# PlantSensor_V02_Schematic.net
KiCad netlist of a schematic drawn in Altium Designer
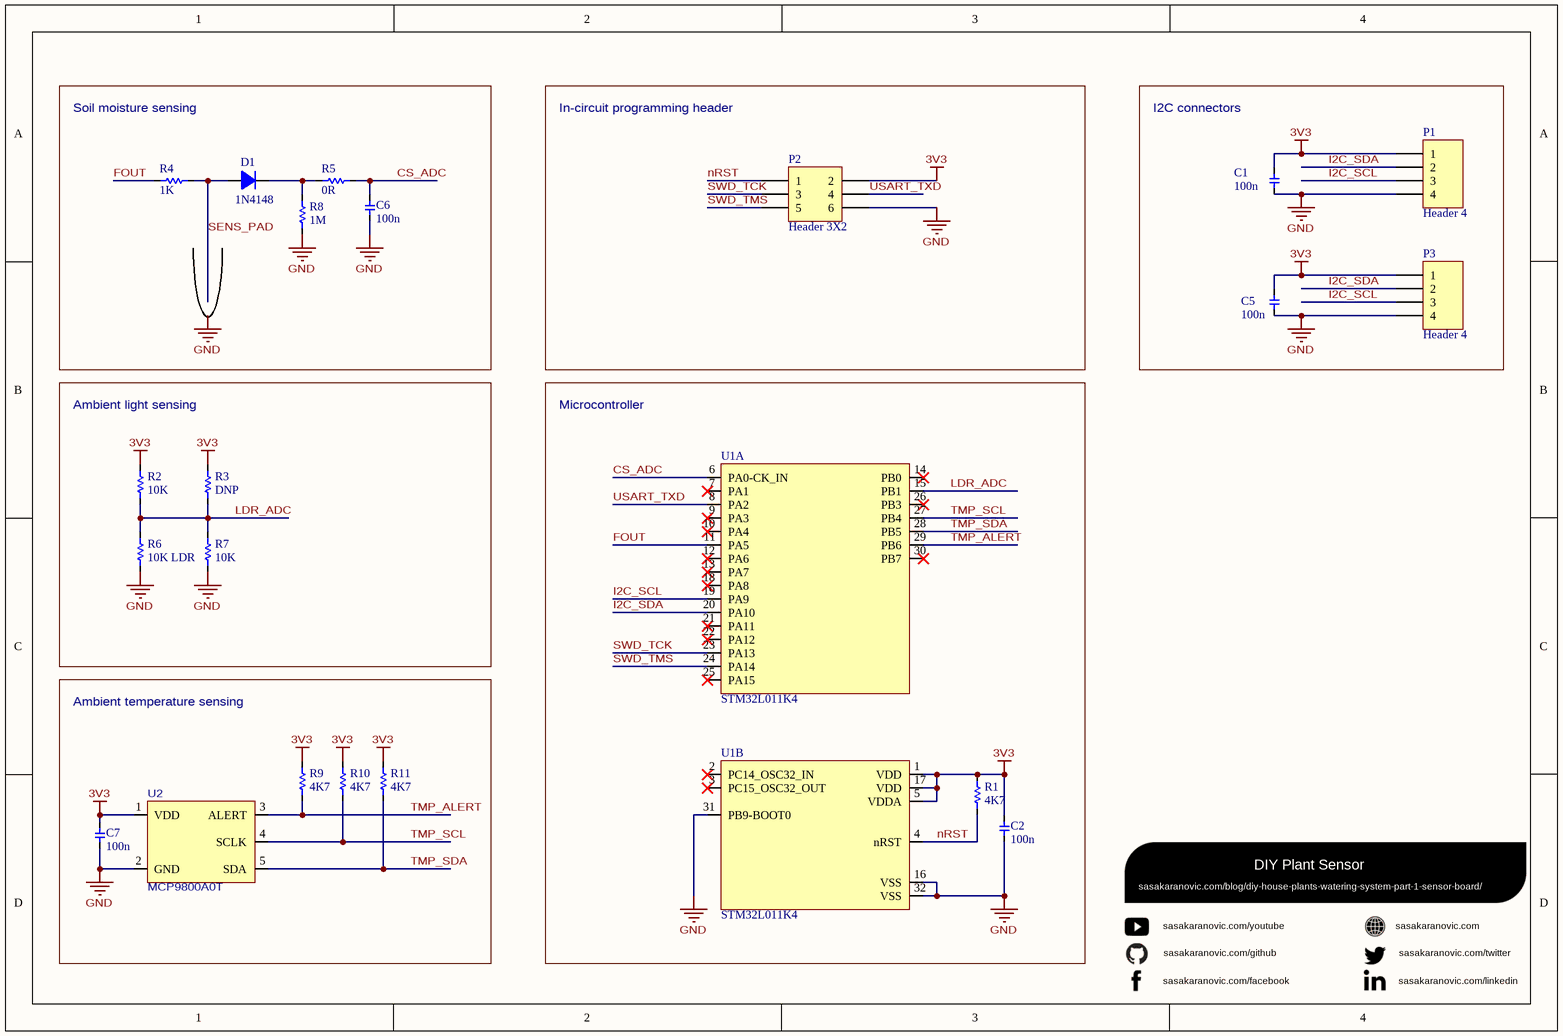
[diagram p0: PlantSensor_V02_Schematic.SchDoc]

(export (version "E")
  (design (tool "Eeschema 10.0.6"))
  (components
    (comp (ref "C1")
      (value "100n")
      (footprint "Moji Footprintovi:0603 - CAP")
      (description "CAP CER 0.1UF 50V X7R 0603")
      (fields
        (field (name "MANUFACTURER") "Samsung Electro-Mechanics")
        (field (name "MANUFACTURER PART NUMBER") "CL10B104KB8NNNL")
      )
      (libsource (lib "Moji Schematici") (part "Cap"))
    )
    (comp (ref "C2")
      (value "100n")
      (footprint "Moji Footprintovi:0603 - CAP")
      (description "CAP CER 0.1UF 50V X7R 0603")
      (fields
        (field (name "MANUFACTURER") "Samsung Electro-Mechanics")
        (field (name "MANUFACTURER PART NUMBER") "CL10B104KB8NNNL")
      )
      (libsource (lib "Moji Schematici") (part "Cap"))
    )
    (comp (ref "C5")
      (value "100n")
      (footprint "Moji Footprintovi:0603 - CAP")
      (description "CAP CER 0.1UF 50V X7R 0603")
      (fields
        (field (name "MANUFACTURER") "Samsung Electro-Mechanics")
        (field (name "MANUFACTURER PART NUMBER") "CL10B104KB8NNNL")
      )
      (libsource (lib "Moji Schematici") (part "Cap"))
    )
    (comp (ref "C6")
      (value "100n")
      (footprint "Moji Footprintovi:0603 - CAP")
      (description "CAP CER 0.1UF 50V X7R 0603")
      (fields
        (field (name "MANUFACTURER") "Samsung Electro-Mechanics")
        (field (name "MANUFACTURER PART NUMBER") "CL10B104KB8NNNL")
      )
      (libsource (lib "Moji Schematici") (part "Cap"))
    )
    (comp (ref "C7")
      (value "100n")
      (footprint "Moji Footprintovi:0603 - CAP")
      (description "CAP CER 0.1UF 50V X7R 0603")
      (fields
        (field (name "MANUFACTURER") "Samsung Electro-Mechanics")
        (field (name "MANUFACTURER PART NUMBER") "CL10B104KB8NNNL")
      )
      (libsource (lib "Moji Schematici") (part "Cap"))
    )
    (comp (ref "D1")
      (value "1N4148")
      (footprint "Moji Footprintovi:SOD123")
      (description "DIODE GEN PURP 100V 300MA SOD123")
      (fields
        (field (name "DISTRIBUTOR PART NUMBER") "1N4148W-FDICT-ND")
        (field (name "MANUFACTURER") "Diodes Incorporated")
      )
      (libsource (lib "Moji Schematici (1)") (part "Diode"))
    )
    (comp (ref "P1")
      (value "Header 4")
      (footprint "Moji Footprintovi:Header 4x1")
      (description "CONN HEADER VERT 4POS 2.54MM")
      (fields
        (field (name "DISTRIBUTOR PART NUMBER") "732-5317-ND")
        (field (name "MANUFACTURER") "Würth Elektronik")
      )
      (libsource (lib "Moji Schematici") (part "Header 4"))
    )
    (comp (ref "P2")
      (value "Header 3X2")
      (footprint "HDR2X3")
      (description "CONN HEADER VERT 6POS 2.54MM")
      (fields
        (field (name "DISTRIBUTOR PART NUMBER") "2057-PH2-06-UA-ND")
        (field (name "MANUFACTURER") "Adam Tech")
      )
      (libsource (lib "Miscellaneous Connectors") (part "Header 3X2"))
    )
    (comp (ref "P3")
      (value "Header 4")
      (footprint "Moji Footprintovi:Header 4x1")
      (description "CONN HEADER VERT 4POS 2.54MM")
      (fields
        (field (name "DISTRIBUTOR PART NUMBER") "732-5317-ND")
        (field (name "MANUFACTURER") "Würth Elektronik")
      )
      (libsource (lib "Moji Schematici") (part "Header 4"))
    )
    (comp (ref "R1")
      (value "4K7")
      (footprint "Moji Footprintovi:0603")
      (description "RES SMD 4.7K OHM 1% 1/10W 0603")
      (fields
        (field (name "DISTRIBUTOR PART NUMBER") "311-4.70KHRCT-ND")
        (field (name "MANUFACTURER") "Yageo")
      )
      (libsource (lib "Moji Schematici") (part "Res"))
    )
    (comp (ref "R2")
      (value "10K")
      (footprint "Moji Footprintovi:0603")
      (description "RES SMD 10K OHM 1% 1/10W 0603")
      (fields (field (name "DISTRIBUTOR PART NUMBER") "311-10KLDCT-ND") (field (name "MANUFACTURER") "Yageo"))
      (libsource (lib "Moji Schematici") (part "Res"))
    )
    (comp (ref "R3")
      (value "DNP")
      (footprint "Moji Footprintovi:0603")
      (description "Resistor")
      (fields (field (name "Comment") "Res"))
      (libsource (lib "Moji Schematici") (part "Res"))
    )
    (comp (ref "R4")
      (value "1K")
      (footprint "Moji Footprintovi:0603")
      (description "RES SMD 1K OHM 1% 1/10W 0603")
      (fields (field (name "DISTRIBUTOR PART NUMBER") "YAG2323CT-ND") (field (name "MANUFACTURER") "Yageo"))
      (libsource (lib "Moji Schematici") (part "Res"))
    )
    (comp (ref "R5")
      (value "0R")
      (footprint "Moji Footprintovi:0603")
      (description "RES SMD 0 OHM JUMPER 1/10W 0603")
      (fields (field (name "DISTRIBUTOR PART NUMBER") "311-0.0LECT-ND") (field (name "MANUFACTURER") "Yageo"))
      (libsource (lib "Moji Schematici") (part "Res"))
    )
    (comp (ref "R6")
      (value "10K LDR")
      (footprint "Moji Footprintovi:Radial0.1 - SMT")
      (description "PHOTOCELL CDS 400OHM TO-18")
      (fields
        (field (name "DISTRIBUTOR PART NUMBER") "NSL-5152-ND")
        (field (name "MANUFACTURER") "Advanced Photonix")
      )
      (libsource (lib "Moji Schematici") (part "Res"))
    )
    (comp (ref "R7")
      (value "10K")
      (footprint "Moji Footprintovi:0603")
      (description "RES SMD 10K OHM 1% 1/10W 0603")
      (fields (field (name "DISTRIBUTOR PART NUMBER") "311-10KLDCT-ND") (field (name "MANUFACTURER") "Yageo"))
      (libsource (lib "Moji Schematici") (part "Res"))
    )
    (comp (ref "R8")
      (value "1M")
      (footprint "Moji Footprintovi:0603")
      (description "RES SMD 1M OHM 5% 1/10W 0603")
      (fields
        (field (name "DISTRIBUTOR PART NUMBER") "311-1.0MGRCT-ND")
        (field (name "MANUFACTURER") "Yageo")
      )
      (libsource (lib "Moji Schematici") (part "Res"))
    )
    (comp (ref "R9")
      (value "4K7")
      (footprint "Moji Footprintovi:0603")
      (description "RES SMD 4.7K OHM 1% 1/10W 0603")
      (fields
        (field (name "DISTRIBUTOR PART NUMBER") "311-4.70KHRCT-ND")
        (field (name "MANUFACTURER") "Yageo")
      )
      (libsource (lib "Moji Schematici") (part "Res"))
    )
    (comp (ref "R10")
      (value "4K7")
      (footprint "Moji Footprintovi:0603")
      (description "RES SMD 4.7K OHM 1% 1/10W 0603")
      (fields
        (field (name "DISTRIBUTOR PART NUMBER") "311-4.70KHRCT-ND")
        (field (name "MANUFACTURER") "Yageo")
      )
      (libsource (lib "Moji Schematici") (part "Res"))
    )
    (comp (ref "R11")
      (value "4K7")
      (footprint "Moji Footprintovi:0603")
      (description "RES SMD 4.7K OHM 1% 1/10W 0603")
      (fields
        (field (name "DISTRIBUTOR PART NUMBER") "311-4.70KHRCT-ND")
        (field (name "MANUFACTURER") "Yageo")
      )
      (libsource (lib "Moji Schematici") (part "Res"))
    )
    (comp (ref "U1")
      (value "STM32L011K4")
      (footprint "Moji Footprintovi:TQFP80P900X900X160-32N")
      (description "IC MCU 32BIT 16KB FLASH 32LQFP")
      (fields
        (field (name "DISTRIBUTOR PART NUMBER") "497-17480-ND")
        (field (name "MANUFACTURER") "STMicroelectronics")
      )
      (libsource (lib "Moji Schematici (1)") (part "STM32L011K4"))
    )
    (comp (ref "U2")
      (value "MCP9800A0T")
      (footprint "Moji Footprintovi:SOT95P270X145-5N")
      (description "SENSOR DIGITAL -55C-125C SOT23-5")
      (fields
        (field (name "MANUFACTURER") "Microchip Technology")
        (field (name "DISTRIBUTOR PART NUMBER") "MCP9800A0T-M/OTCT-ND")
      )
      (libsource (lib "Moji Schematici") (part "MCP9800A0T-M/OT"))
    )
  )
  (nets
    (net (code "1") (name "/CS_ADC") (class "Default")
      (node (ref "C6") (pin "2") (pinfunction "2_2") (pintype "passive"))
      (node (ref "R5") (pin "2") (pinfunction "2_2") (pintype "passive"))
      (node (ref "U1") (pin "6") (pinfunction "PA0-CK_IN_6") (pintype "passive"))
    )
    (net (code "2") (name "/FOUT") (class "Default")
      (node (ref "R4") (pin "1") (pinfunction "1_1") (pintype "passive"))
      (node (ref "U1") (pin "11") (pinfunction "PA5_11") (pintype "passive"))
    )
    (net (code "3") (name "/I2C_SCL") (class "Default")
      (node (ref "P1") (pin "3") (pinfunction "3_3") (pintype "passive"))
      (node (ref "P3") (pin "3") (pinfunction "3_3") (pintype "passive"))
      (node (ref "U1") (pin "19") (pinfunction "PA9_19") (pintype "passive"))
    )
    (net (code "4") (name "/I2C_SDA") (class "Default")
      (node (ref "P1") (pin "2") (pinfunction "2_2") (pintype "passive"))
      (node (ref "P3") (pin "2") (pinfunction "2_2") (pintype "passive"))
      (node (ref "U1") (pin "20") (pinfunction "PA10_20") (pintype "passive"))
    )
    (net (code "5") (name "/LDR_ADC") (class "Default")
      (node (ref "R2") (pin "1") (pinfunction "1_1") (pintype "passive"))
      (node (ref "R3") (pin "1") (pinfunction "1_1") (pintype "passive"))
      (node (ref "R6") (pin "2") (pinfunction "2_2") (pintype "passive"))
      (node (ref "R7") (pin "2") (pinfunction "2_2") (pintype "passive"))
      (node (ref "U1") (pin "15") (pinfunction "PB1_15") (pintype "passive"))
    )
    (net (code "6") (name "/SENS_PAD") (class "Default")
      (node (ref "D1") (pin "A") (pinfunction "A_A") (pintype "passive"))
      (node (ref "R4") (pin "2") (pinfunction "2_2") (pintype "passive"))
    )
    (net (code "7") (name "/SWD_TCK") (class "Default")
      (node (ref "P2") (pin "3") (pinfunction "3_3") (pintype "passive"))
      (node (ref "U1") (pin "23") (pinfunction "PA13_23") (pintype "passive"))
    )
    (net (code "8") (name "/SWD_TMS") (class "Default")
      (node (ref "P2") (pin "5") (pinfunction "5_5") (pintype "passive"))
      (node (ref "U1") (pin "24") (pinfunction "PA14_24") (pintype "passive"))
    )
    (net (code "9") (name "/TMP_ALERT") (class "Default")
      (node (ref "R9") (pin "1") (pinfunction "1_1") (pintype "passive"))
      (node (ref "U1") (pin "29") (pinfunction "PB6_29") (pintype "passive"))
      (node (ref "U2") (pin "3") (pinfunction "ALERT_3") (pintype "passive"))
    )
    (net (code "10") (name "/TMP_SCL") (class "Default")
      (node (ref "R10") (pin "1") (pinfunction "1_1") (pintype "passive"))
      (node (ref "U1") (pin "27") (pinfunction "PB4_27") (pintype "passive"))
      (node (ref "U2") (pin "4") (pinfunction "SCLK_4") (pintype "passive"))
    )
    (net (code "11") (name "/TMP_SDA") (class "Default")
      (node (ref "R11") (pin "1") (pinfunction "1_1") (pintype "passive"))
      (node (ref "U1") (pin "28") (pinfunction "PB5_28") (pintype "passive"))
      (node (ref "U2") (pin "5") (pinfunction "SDA_5") (pintype "passive"))
    )
    (net (code "12") (name "/USART_TXD") (class "Default")
      (node (ref "P2") (pin "4") (pinfunction "4_4") (pintype "passive"))
      (node (ref "U1") (pin "8") (pinfunction "PA2_8") (pintype "passive"))
    )
    (net (code "13") (name "/nRST") (class "Default")
      (node (ref "P2") (pin "1") (pinfunction "1_1") (pintype "passive"))
      (node (ref "R1") (pin "1") (pinfunction "1_1") (pintype "passive"))
      (node (ref "U1") (pin "4") (pinfunction "nRST_4") (pintype "passive"))
    )
    (net (code "14") (name "3V3") (class "Default")
      (node (ref "C1") (pin "2") (pinfunction "2_2") (pintype "passive"))
      (node (ref "C2") (pin "2") (pinfunction "2_2") (pintype "passive"))
      (node (ref "C5") (pin "2") (pinfunction "2_2") (pintype "passive"))
      (node (ref "C7") (pin "2") (pinfunction "2_2") (pintype "passive"))
      (node (ref "P1") (pin "1") (pinfunction "1_1") (pintype "passive"))
      (node (ref "P2") (pin "2") (pinfunction "2_2") (pintype "passive"))
      (node (ref "P3") (pin "1") (pinfunction "1_1") (pintype "passive"))
      (node (ref "R1") (pin "2") (pinfunction "2_2") (pintype "passive"))
      (node (ref "R10") (pin "2") (pinfunction "2_2") (pintype "passive"))
      (node (ref "R11") (pin "2") (pinfunction "2_2") (pintype "passive"))
      (node (ref "R2") (pin "2") (pinfunction "2_2") (pintype "passive"))
      (node (ref "R3") (pin "2") (pinfunction "2_2") (pintype "passive"))
      (node (ref "R9") (pin "2") (pinfunction "2_2") (pintype "passive"))
      (node (ref "U1") (pin "1") (pinfunction "VDD_1") (pintype "passive"))
      (node (ref "U1") (pin "17") (pinfunction "VDD_17") (pintype "passive"))
      (node (ref "U1") (pin "5") (pinfunction "VDDA_5") (pintype "passive"))
      (node (ref "U2") (pin "1") (pinfunction "VDD_1") (pintype "passive"))
    )
    (net (code "15") (name "GND") (class "Default")
      (node (ref "C1") (pin "1") (pinfunction "1_1") (pintype "passive"))
      (node (ref "C2") (pin "1") (pinfunction "1_1") (pintype "passive"))
      (node (ref "C5") (pin "1") (pinfunction "1_1") (pintype "passive"))
      (node (ref "C6") (pin "1") (pinfunction "1_1") (pintype "passive"))
      (node (ref "C7") (pin "1") (pinfunction "1_1") (pintype "passive"))
      (node (ref "P1") (pin "4") (pinfunction "4_4") (pintype "passive"))
      (node (ref "P2") (pin "6") (pinfunction "6_6") (pintype "passive"))
      (node (ref "P3") (pin "4") (pinfunction "4_4") (pintype "passive"))
      (node (ref "R6") (pin "1") (pinfunction "1_1") (pintype "passive"))
      (node (ref "R7") (pin "1") (pinfunction "1_1") (pintype "passive"))
      (node (ref "R8") (pin "1") (pinfunction "1_1") (pintype "passive"))
      (node (ref "U1") (pin "16") (pinfunction "VSS_16") (pintype "passive"))
      (node (ref "U1") (pin "31") (pinfunction "PB9-BOOT0_31") (pintype "passive"))
      (node (ref "U1") (pin "32") (pinfunction "VSS_32") (pintype "passive"))
      (node (ref "U2") (pin "2") (pinfunction "GND_2") (pintype "passive"))
    )
    (net (code "16") (name "Net-(D1-PadK)") (class "Default")
      (node (ref "D1") (pin "K") (pinfunction "K_K") (pintype "passive"))
      (node (ref "R5") (pin "1") (pinfunction "1_1") (pintype "passive"))
      (node (ref "R8") (pin "2") (pinfunction "2_2") (pintype "passive"))
    )
    (net (code "17") (name "unconnected-(U1A-PA1-Pad7)") (class "Default")
      (node (ref "U1") (pin "7") (pinfunction "PA1_7") (pintype "passive+no_connect"))
    )
    (net (code "18") (name "unconnected-(U1A-PA3-Pad9)") (class "Default")
      (node (ref "U1") (pin "9") (pinfunction "PA3_9") (pintype "passive+no_connect"))
    )
    (net (code "19") (name "unconnected-(U1A-PA4-Pad10)") (class "Default")
      (node (ref "U1") (pin "10") (pinfunction "PA4_10") (pintype "passive+no_connect"))
    )
    (net (code "20") (name "unconnected-(U1A-PA6-Pad12)") (class "Default")
      (node (ref "U1") (pin "12") (pinfunction "PA6_12") (pintype "passive+no_connect"))
    )
    (net (code "21") (name "unconnected-(U1A-PA7-Pad13)") (class "Default")
      (node (ref "U1") (pin "13") (pinfunction "PA7_13") (pintype "passive+no_connect"))
    )
    (net (code "22") (name "unconnected-(U1A-PA8-Pad18)") (class "Default")
      (node (ref "U1") (pin "18") (pinfunction "PA8_18") (pintype "passive+no_connect"))
    )
    (net (code "23") (name "unconnected-(U1A-PA11-Pad21)") (class "Default")
      (node (ref "U1") (pin "21") (pinfunction "PA11_21") (pintype "passive+no_connect"))
    )
    (net (code "24") (name "unconnected-(U1A-PA12-Pad22)") (class "Default")
      (node (ref "U1") (pin "22") (pinfunction "PA12_22") (pintype "passive+no_connect"))
    )
    (net (code "25") (name "unconnected-(U1A-PA15-Pad25)") (class "Default")
      (node (ref "U1") (pin "25") (pinfunction "PA15_25") (pintype "passive+no_connect"))
    )
    (net (code "26") (name "unconnected-(U1A-PB0-Pad14)") (class "Default")
      (node (ref "U1") (pin "14") (pinfunction "PB0_14") (pintype "passive+no_connect"))
    )
    (net (code "27") (name "unconnected-(U1A-PB3-Pad26)") (class "Default")
      (node (ref "U1") (pin "26") (pinfunction "PB3_26") (pintype "passive+no_connect"))
    )
    (net (code "28") (name "unconnected-(U1A-PB7-Pad30)") (class "Default")
      (node (ref "U1") (pin "30") (pinfunction "PB7_30") (pintype "passive+no_connect"))
    )
    (net (code "29") (name "unconnected-(U1B-PC14_OSC32_IN-Pad2)") (class "Default")
      (node (ref "U1") (pin "2") (pinfunction "PC14_OSC32_IN_2") (pintype "passive+no_connect"))
    )
    (net (code "30") (name "unconnected-(U1B-PC15_OSC32_OUT-Pad3)") (class "Default")
      (node (ref "U1") (pin "3") (pinfunction "PC15_OSC32_OUT_3") (pintype "passive+no_connect"))
    )
  )
)
